# MOSFET_V3.net
KiCad netlist of a schematic drawn in Altium Designer
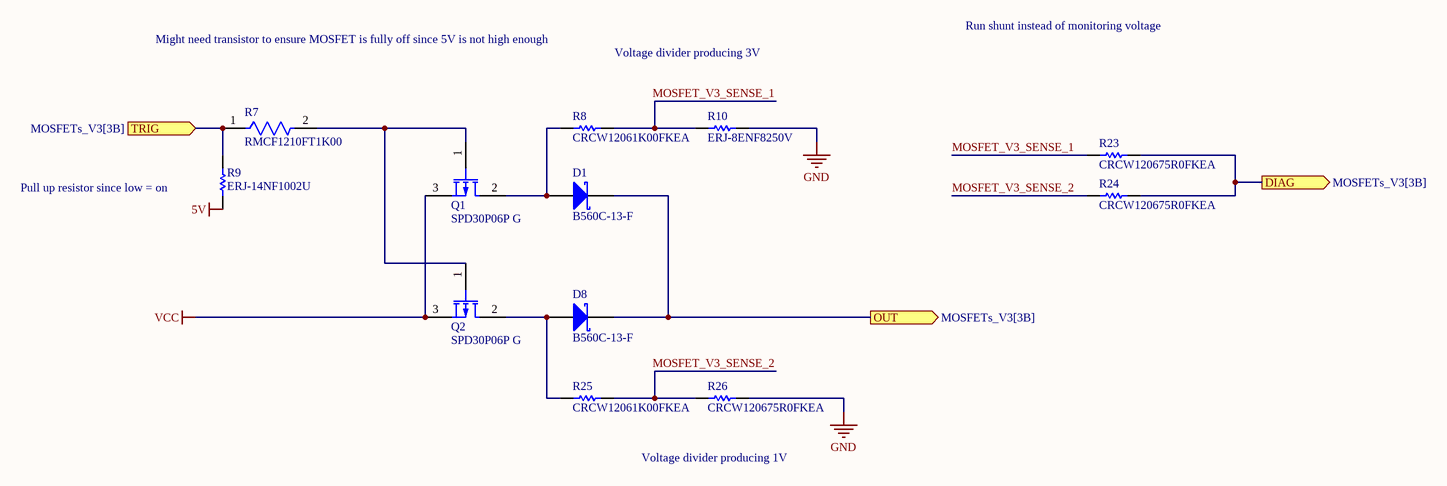
[diagram p0: MOSFET_V3.SchDoc]

(export (version "E")
  (design (tool "Eeschema 10.0.6"))
  (components
    (comp (ref "D1")
      (value "B560C-13-F")
      (footprint "DIOD-B5X0C-2_M")
      (description "Schottky Barrier Rectifier, 5 A, 60 V, -55 to 125 degC, 2-Pin SMD, RoHS, Tape and Reel")
      (fields (field (name "MANUFACTURER") "DiodesIncorporated"))
      (libsource (lib "Altium Content Vault") (part "DSKY-KA-2"))
    )
    (comp (ref "D8")
      (value "B560C-13-F")
      (footprint "DIOD-B5X0C-2_M")
      (description "Schottky Barrier Rectifier, 5 A, 60 V, -55 to 125 degC, 2-Pin SMD, RoHS, Tape and Reel")
      (fields (field (name "MANUFACTURER") "DiodesIncorporated"))
      (libsource (lib "Altium Content Vault") (part "DSKY-KA-2"))
    )
    (comp (ref "Q1")
      (value "SPD30P06P G")
      (footprint "INF-PG-TO252-3-1_N")
      (description "P-Channel SIPMOS Power-Transistor, -60 V VDS, -30 A ID, -55 to 175 degC, PG-TO252-3-1, Reel, Green")
      (fields (field (name "MANUFACTURER") "Infineon"))
      (libsource (lib "Altium Content Vault") (part "INF-SPD30P06PG-PG-TO252-3-313-3"))
    )
    (comp (ref "Q2")
      (value "SPD30P06P G")
      (footprint "INF-PG-TO252-3-1_N")
      (description "P-Channel SIPMOS Power-Transistor, -60 V VDS, -30 A ID, -55 to 175 degC, PG-TO252-3-1, Reel, Green")
      (fields (field (name "MANUFACTURER") "Infineon"))
      (libsource (lib "Altium Content Vault") (part "INF-SPD30P06PG-PG-TO252-3-313-3"))
    )
    (comp (ref "R7")
      (value "RMCF1210FT1K00")
      (footprint "FP-RMCF1210-IPC_A")
      (description "1kΩ ±1% 0.5W 1210 Thick Film Chip Resistor AEC-Q200 compliant")
      (fields (field (name "TOLERANCE") "1%"))
      (libsource (lib "Altium Content Vault") (part "1029c3af85768c4190bb7ad29bc67b5"))
    )
    (comp (ref "R8")
      (value "CRCW12061K00FKEA")
      (footprint "RESC3216X60X45ML15T20")
      (description "Chip Resistor, 1 KOhm, +/- 1%, 0.25 W, -55 to 155 degC, 1206 (3216 Metric), RoHS, Tape and Reel")
      (fields (field (name "MANUFACTURER") "Vishay Semiconductor") (field (name "TOLERANCE") "1%"))
      (libsource (lib "Altium Content Vault") (part "RES-2"))
    )
    (comp (ref "R9")
      (value "ERJ-14NF1002U")
      (footprint "RESC3225X70X50NL20T20")
      (fields (field (name "MANUFACTURER") "Panasonic"))
      (libsource (lib "Altium Content Vault") (part "RES"))
    )
    (comp (ref "R10")
      (value "ERJ-8ENF8250V")
      (footprint "RESC3216X70X50LL05T20")
      (fields (field (name "MANUFACTURER") "Panasonic"))
      (libsource (lib "Altium Content Vault") (part "RES"))
    )
    (comp (ref "R23")
      (value "CRCW120675R0FKEA")
      (footprint "RESC3216X60X45NL10T20")
      (fields (field (name "MANUFACTURER") "Vishay Dale"))
      (libsource (lib "Altium Content Vault") (part "RES"))
    )
    (comp (ref "R24")
      (value "CRCW120675R0FKEA")
      (footprint "RESC3216X60X45NL10T20")
      (fields (field (name "MANUFACTURER") "Vishay Dale"))
      (libsource (lib "Altium Content Vault") (part "RES"))
    )
    (comp (ref "R25")
      (value "CRCW12061K00FKEA")
      (footprint "RESC3216X60X45ML15T20")
      (description "Chip Resistor, 1 KOhm, +/- 1%, 0.25 W, -55 to 155 degC, 1206 (3216 Metric), RoHS, Tape and Reel")
      (fields (field (name "MANUFACTURER") "Vishay Semiconductor") (field (name "TOLERANCE") "1%"))
      (libsource (lib "Altium Content Vault") (part "RES-2"))
    )
    (comp (ref "R26")
      (value "CRCW120675R0FKEA")
      (footprint "RESC3216X60X45NL10T20")
      (fields (field (name "MANUFACTURER") "Vishay Dale"))
      (libsource (lib "Altium Content Vault") (part "RES"))
    )
  )
  (nets
    (net (code "1") (name "/DIAG") (class "Default")
      (node (ref "R23") (pin "2") (pinfunction "2_2") (pintype "passive"))
      (node (ref "R24") (pin "2") (pinfunction "2_2") (pintype "passive"))
    )
    (net (code "2") (name "/MOSFET_V3_SENSE_1") (class "Default")
      (node (ref "R10") (pin "1") (pinfunction "1_1") (pintype "passive"))
      (node (ref "R23") (pin "1") (pinfunction "1_1") (pintype "passive"))
      (node (ref "R8") (pin "2") (pinfunction "2_2") (pintype "passive"))
    )
    (net (code "3") (name "/MOSFET_V3_SENSE_2") (class "Default")
      (node (ref "R24") (pin "1") (pinfunction "1_1") (pintype "passive"))
      (node (ref "R25") (pin "2") (pinfunction "2_2") (pintype "passive"))
      (node (ref "R26") (pin "1") (pinfunction "1_1") (pintype "passive"))
    )
    (net (code "4") (name "/OUT") (class "Default")
      (node (ref "D1") (pin "1") (pinfunction "K_1") (pintype "passive"))
      (node (ref "D8") (pin "1") (pinfunction "K_1") (pintype "passive"))
    )
    (net (code "5") (name "/TRIG") (class "Default")
      (node (ref "R7") (pin "1") (pinfunction "1_1") (pintype "passive"))
      (node (ref "R9") (pin "1") (pinfunction "1_1") (pintype "passive"))
    )
    (net (code "6") (name "5V") (class "Default")
      (node (ref "R9") (pin "2") (pinfunction "2_2") (pintype "passive"))
    )
    (net (code "7") (name "GND") (class "Default")
      (node (ref "R10") (pin "2") (pinfunction "2_2") (pintype "passive"))
      (node (ref "R26") (pin "2") (pinfunction "2_2") (pintype "passive"))
    )
    (net (code "8") (name "Net-(D1-A)") (class "Default")
      (node (ref "D1") (pin "2") (pinfunction "A_2") (pintype "passive"))
      (node (ref "Q1") (pin "2") (pinfunction "D_2") (pintype "passive"))
      (node (ref "R8") (pin "1") (pinfunction "1_1") (pintype "passive"))
    )
    (net (code "9") (name "Net-(D8-A)") (class "Default")
      (node (ref "D8") (pin "2") (pinfunction "A_2") (pintype "passive"))
      (node (ref "Q2") (pin "2") (pinfunction "D_2") (pintype "passive"))
      (node (ref "R25") (pin "1") (pinfunction "1_1") (pintype "passive"))
    )
    (net (code "10") (name "Net-(Q1-G)") (class "Default")
      (node (ref "Q1") (pin "1") (pinfunction "G_1") (pintype "passive"))
      (node (ref "Q2") (pin "1") (pinfunction "G_1") (pintype "passive"))
      (node (ref "R7") (pin "2") (pinfunction "2_2") (pintype "passive"))
    )
    (net (code "11") (name "VCC") (class "Default")
      (node (ref "Q1") (pin "3") (pinfunction "S_3") (pintype "passive"))
      (node (ref "Q2") (pin "3") (pinfunction "S_3") (pintype "passive"))
    )
  )
)
